# speedmeter.net
KiCad netlist of a schematic drawn in EAGLE
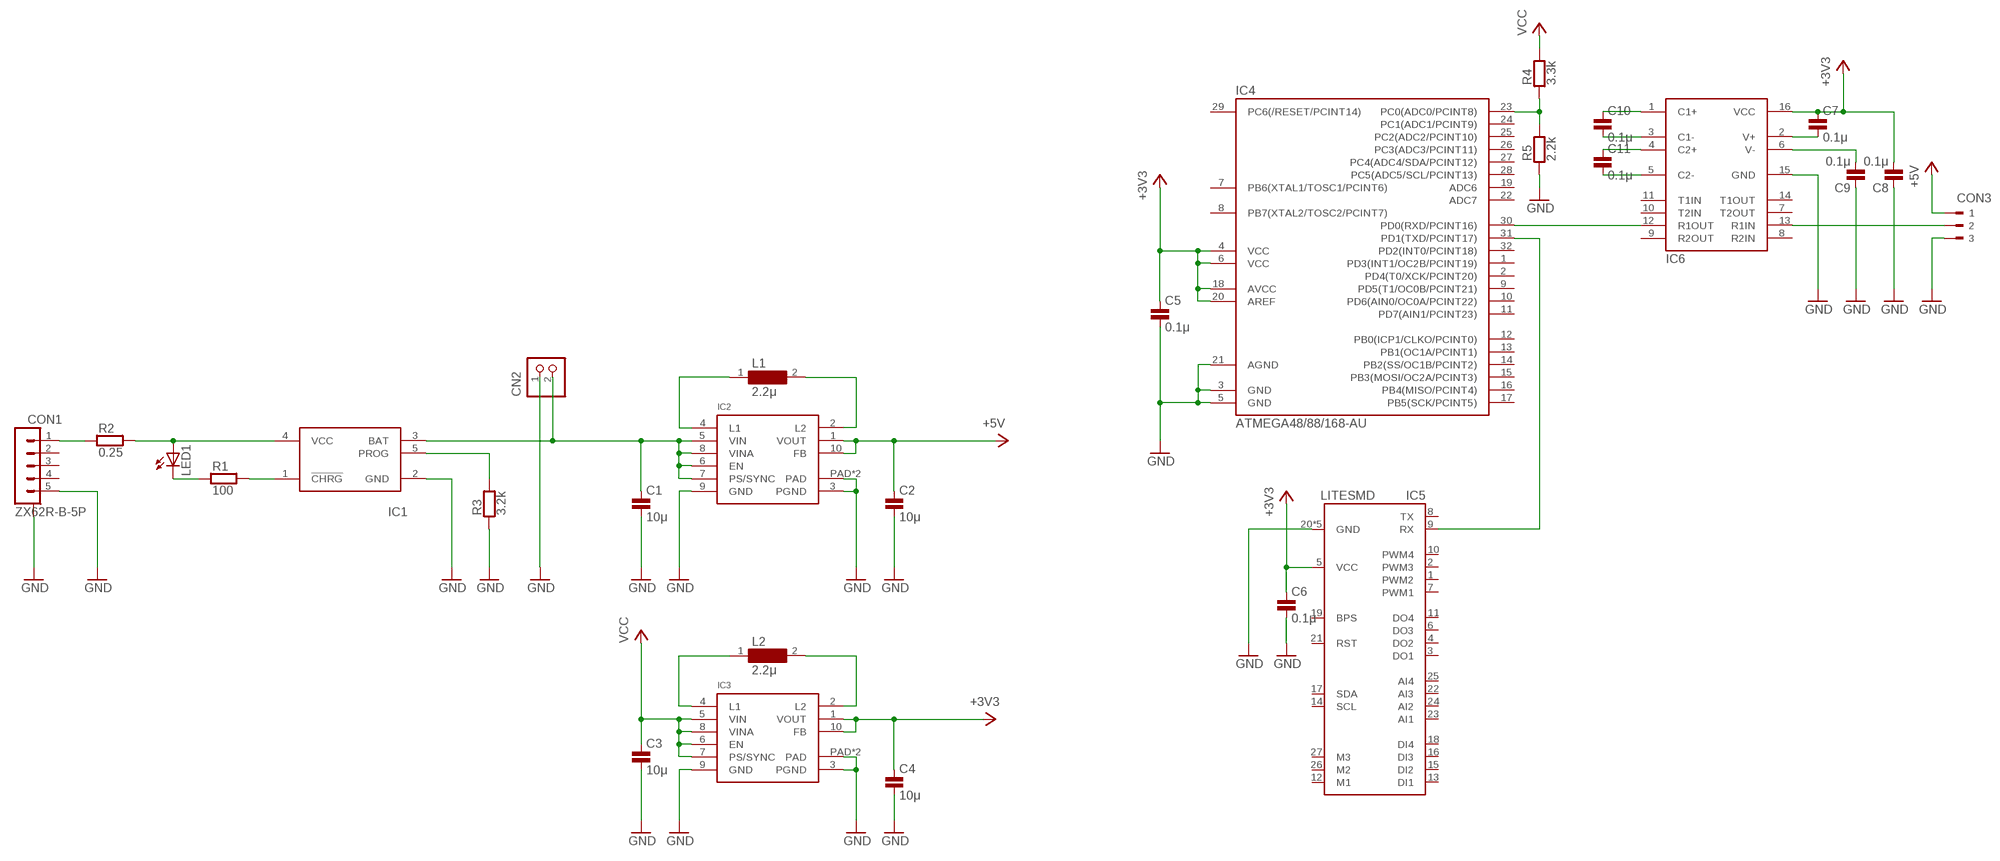
[diagram p0: schematic, sheet 1]

(export (version "E")
  (design (tool "Eeschema 10.0.6"))
  (components
    (comp (ref "C1")
      (value "10μ")
      (footprint "eagle-import:0603")
      (libsource (lib "eagle-import") (part "C0603"))
    )
    (comp (ref "C2")
      (value "10μ")
      (footprint "eagle-import:0603")
      (libsource (lib "eagle-import") (part "C0603"))
    )
    (comp (ref "C3")
      (value "10μ")
      (footprint "eagle-import:0603")
      (libsource (lib "eagle-import") (part "C0603"))
    )
    (comp (ref "C4")
      (value "10μ")
      (footprint "eagle-import:0603")
      (libsource (lib "eagle-import") (part "C0603"))
    )
    (comp (ref "C5")
      (value "0.1μ")
      (footprint "eagle-import:0603")
      (libsource (lib "eagle-import") (part "C0603"))
    )
    (comp (ref "C6")
      (value "0.1μ")
      (footprint "eagle-import:0603")
      (libsource (lib "eagle-import") (part "C0603"))
    )
    (comp (ref "C7")
      (value "0.1μ")
      (footprint "eagle-import:0603")
      (libsource (lib "eagle-import") (part "untitled-2_C0603"))
    )
    (comp (ref "C8")
      (value "0.1μ")
      (footprint "eagle-import:0603")
      (libsource (lib "eagle-import") (part "untitled-2_C0603"))
    )
    (comp (ref "C9")
      (value "0.1μ")
      (footprint "eagle-import:0603")
      (libsource (lib "eagle-import") (part "untitled-2_C0603"))
    )
    (comp (ref "C10")
      (value "0.1μ")
      (footprint "eagle-import:0603")
      (libsource (lib "eagle-import") (part "untitled-2_C0603"))
    )
    (comp (ref "C11")
      (value "0.1μ")
      (footprint "eagle-import:0603")
      (libsource (lib "eagle-import") (part "untitled-2_C0603"))
    )
    (comp (ref "CN2")
      (value "S2B-PH-K-S")
      (footprint "eagle-import:S2B-PH-K-S")
      (libsource (lib "eagle-import") (part "S2B-PH-K-S"))
    )
    (comp (ref "CON1")
      (value "ZX62R-B-5P")
      (footprint "eagle-import:MICRO-B")
      (libsource (lib "eagle-import") (part "ZX62R-B-5P"))
    )
    (comp (ref "CON3")
      (value "180-3")
      (footprint "eagle-import:180-3")
      (libsource (lib "eagle-import") (part "180-3"))
    )
    (comp (ref "IC1")
      (value "LTC4054")
      (footprint "eagle-import:TSOT23-5")
      (libsource (lib "eagle-import") (part "LTC4054"))
    )
    (comp (ref "IC2")
      (value "TPS6300XDRCT")
      (footprint "eagle-import:S-PVSON-N10")
      (libsource (lib "eagle-import") (part "TPS6300XDRCT"))
    )
    (comp (ref "IC3")
      (value "TPS6300XDRCT")
      (footprint "eagle-import:S-PVSON-N10")
      (libsource (lib "eagle-import") (part "TPS6300XDRCT"))
    )
    (comp (ref "IC4")
      (value "ATMEGA48/88/168-AU")
      (footprint "eagle-import:TQFP32-08")
      (libsource (lib "eagle-import") (part "ATMEGA48/88/168-AU"))
    )
    (comp (ref "IC5")
      (value "LITESMD")
      (footprint "eagle-import:LITE")
      (libsource (lib "eagle-import") (part "LITESMD"))
    )
    (comp (ref "IC6")
      (value "ADM3202ARN")
      (footprint "eagle-import:SOP16")
      (libsource (lib "eagle-import") (part "ADM3202ARN"))
    )
    (comp (ref "L1")
      (value "2.2μ")
      (footprint "eagle-import:VLF4012ST")
      (libsource (lib "eagle-import") (part "VLF4012ST"))
    )
    (comp (ref "L2")
      (value "2.2μ")
      (footprint "eagle-import:VLF4012ST")
      (libsource (lib "eagle-import") (part "VLF4012ST"))
    )
    (comp (ref "LED1")
      (value "LEDSML0603")
      (footprint "eagle-import:SML0603")
      (libsource (lib "eagle-import") (part "LEDSML0603"))
    )
    (comp (ref "R1")
      (value "100")
      (footprint "eagle-import:0603")
      (libsource (lib "eagle-import") (part "R0603"))
    )
    (comp (ref "R2")
      (value "0.25")
      (footprint "eagle-import:0603")
      (libsource (lib "eagle-import") (part "R0603"))
    )
    (comp (ref "R3")
      (value "3.2k")
      (footprint "eagle-import:0603")
      (libsource (lib "eagle-import") (part "R0603"))
    )
    (comp (ref "R4")
      (value "3.3k")
      (footprint "eagle-import:0603")
      (libsource (lib "eagle-import") (part "R0603"))
    )
    (comp (ref "R5")
      (value "2.2k")
      (footprint "eagle-import:0603")
      (libsource (lib "eagle-import") (part "R0603"))
    )
  )
  (nets
    (net (code "1") (name "+3V3") (class "Default")
      (node (ref "C4") (pin "1") (pinfunction "P$1_1") (pintype "passive"))
      (node (ref "C5") (pin "1") (pinfunction "P$1_1") (pintype "passive"))
      (node (ref "C6") (pin "1") (pinfunction "P$1_1") (pintype "passive"))
      (node (ref "C7") (pin "1") (pinfunction "P$1_1") (pintype "passive"))
      (node (ref "C8") (pin "2") (pinfunction "P$2_2") (pintype "passive"))
      (node (ref "IC3") (pin "1") (pinfunction "VOUT_1") (pintype "output"))
      (node (ref "IC3") (pin "10") (pinfunction "FB_10") (pintype "input"))
      (node (ref "IC4") (pin "18") (pinfunction "AVCC_18") (pintype "passive"))
      (node (ref "IC4") (pin "20") (pinfunction "AREF_20") (pintype "passive"))
      (node (ref "IC4") (pin "4") (pinfunction "VCC_4") (pintype "power_in"))
      (node (ref "IC4") (pin "6") (pinfunction "VCC_6") (pintype "power_in"))
      (node (ref "IC5") (pin "5") (pinfunction "VCC_5") (pintype "power_in"))
      (node (ref "IC6") (pin "16") (pinfunction "VCC_16") (pintype "bidirectional"))
    )
    (net (code "2") (name "+5V") (class "Default")
      (node (ref "C2") (pin "1") (pinfunction "P$1_1") (pintype "passive"))
      (node (ref "CON3") (pin "1") (pinfunction "1_1") (pintype "passive"))
      (node (ref "IC2") (pin "1") (pinfunction "VOUT_1") (pintype "output"))
      (node (ref "IC2") (pin "10") (pinfunction "FB_10") (pintype "input"))
    )
    (net (code "3") (name "GND") (class "Default")
      (node (ref "C1") (pin "2") (pinfunction "P$2_2") (pintype "passive"))
      (node (ref "C2") (pin "2") (pinfunction "P$2_2") (pintype "passive"))
      (node (ref "C3") (pin "2") (pinfunction "P$2_2") (pintype "passive"))
      (node (ref "C4") (pin "2") (pinfunction "P$2_2") (pintype "passive"))
      (node (ref "C5") (pin "2") (pinfunction "P$2_2") (pintype "passive"))
      (node (ref "C6") (pin "2") (pinfunction "P$2_2") (pintype "passive"))
      (node (ref "C8") (pin "1") (pinfunction "P$1_1") (pintype "passive"))
      (node (ref "C9") (pin "1") (pinfunction "P$1_1") (pintype "passive"))
      (node (ref "CN2") (pin "1") (pinfunction "1_1") (pintype "passive"))
      (node (ref "CON1") (pin "5") (pinfunction "1.VBUS_5") (pintype "passive"))
      (node (ref "CON1") (pin "CASE@1") (pinfunction "P$1_CASE@1") (pintype "bidirectional"))
      (node (ref "CON1") (pin "CASE@2") (pinfunction "P$1_CASE@2") (pintype "bidirectional"))
      (node (ref "CON1") (pin "CASE@3") (pinfunction "P$1_CASE@3") (pintype "bidirectional"))
      (node (ref "CON1") (pin "CASE@4") (pinfunction "P$1_CASE@4") (pintype "bidirectional"))
      (node (ref "CON3") (pin "3") (pinfunction "3_3") (pintype "passive"))
      (node (ref "IC1") (pin "2") (pinfunction "GND_2") (pintype "power_in"))
      (node (ref "IC2") (pin "3") (pinfunction "PGND_3") (pintype "power_in"))
      (node (ref "IC2") (pin "9") (pinfunction "GND_9") (pintype "power_in"))
      (node (ref "IC2") (pin "PAD") (pinfunction "PAD_PAD") (pintype "power_in"))
      (node (ref "IC2") (pin "PAD@1") (pinfunction "PAD_PAD@1") (pintype "power_in"))
      (node (ref "IC3") (pin "3") (pinfunction "PGND_3") (pintype "power_in"))
      (node (ref "IC3") (pin "9") (pinfunction "GND_9") (pintype "power_in"))
      (node (ref "IC3") (pin "PAD") (pinfunction "PAD_PAD") (pintype "power_in"))
      (node (ref "IC3") (pin "PAD@1") (pinfunction "PAD_PAD@1") (pintype "power_in"))
      (node (ref "IC4") (pin "21") (pinfunction "AGND_21") (pintype "power_in"))
      (node (ref "IC4") (pin "3") (pinfunction "GND_3") (pintype "power_in"))
      (node (ref "IC4") (pin "5") (pinfunction "GND_5") (pintype "power_in"))
      (node (ref "IC5") (pin "20") (pinfunction "GND_20") (pintype "power_in"))
      (node (ref "IC5") (pin "28") (pinfunction "GND_28") (pintype "power_in"))
      (node (ref "IC5") (pin "30") (pinfunction "GND_30") (pintype "power_in"))
      (node (ref "IC5") (pin "31") (pinfunction "GND_31") (pintype "power_in"))
      (node (ref "IC5") (pin "32") (pinfunction "GND_32") (pintype "power_in"))
      (node (ref "IC6") (pin "15") (pinfunction "GND_15") (pintype "bidirectional"))
      (node (ref "R3") (pin "1") (pinfunction "P$1_1") (pintype "passive"))
      (node (ref "R5") (pin "1") (pinfunction "P$1_1") (pintype "passive"))
    )
    (net (code "4") (name "Net-(C7-P$2)") (class "Default")
      (node (ref "C7") (pin "2") (pinfunction "P$2_2") (pintype "passive"))
      (node (ref "IC6") (pin "2") (pinfunction "V+_2") (pintype "bidirectional"))
    )
    (net (code "5") (name "Net-(C9-P$2)") (class "Default")
      (node (ref "C9") (pin "2") (pinfunction "P$2_2") (pintype "passive"))
      (node (ref "IC6") (pin "6") (pinfunction "V-_6") (pintype "bidirectional"))
    )
    (net (code "6") (name "Net-(C10-P$1)") (class "Default")
      (node (ref "C10") (pin "1") (pinfunction "P$1_1") (pintype "passive"))
      (node (ref "IC6") (pin "1") (pinfunction "C1+_1") (pintype "bidirectional"))
    )
    (net (code "7") (name "Net-(C10-P$2)") (class "Default")
      (node (ref "C10") (pin "2") (pinfunction "P$2_2") (pintype "passive"))
      (node (ref "IC6") (pin "3") (pinfunction "C1-_3") (pintype "bidirectional"))
    )
    (net (code "8") (name "Net-(C11-P$1)") (class "Default")
      (node (ref "C11") (pin "1") (pinfunction "P$1_1") (pintype "passive"))
      (node (ref "IC6") (pin "4") (pinfunction "C2+_4") (pintype "bidirectional"))
    )
    (net (code "9") (name "Net-(C11-P$2)") (class "Default")
      (node (ref "C11") (pin "2") (pinfunction "P$2_2") (pintype "passive"))
      (node (ref "IC6") (pin "5") (pinfunction "C2-_5") (pintype "bidirectional"))
    )
    (net (code "10") (name "Net-(CON1-5.GND)") (class "Default")
      (node (ref "CON1") (pin "1") (pinfunction "5.GND_1") (pintype "passive"))
      (node (ref "R2") (pin "1") (pinfunction "P$1_1") (pintype "passive"))
    )
    (net (code "11") (name "Net-(IC1-PROG)") (class "Default")
      (node (ref "IC1") (pin "5") (pinfunction "PROG_5") (pintype "passive"))
      (node (ref "R3") (pin "2") (pinfunction "P$2_2") (pintype "passive"))
    )
    (net (code "12") (name "Net-(IC1-VCC)") (class "Default")
      (node (ref "IC1") (pin "4") (pinfunction "VCC_4") (pintype "power_in"))
      (node (ref "LED1") (pin "A") (pinfunction "A_A") (pintype "passive"))
      (node (ref "R2") (pin "2") (pinfunction "P$2_2") (pintype "passive"))
    )
    (net (code "13") (name "Net-(IC1-~{CHRG})") (class "Default")
      (node (ref "IC1") (pin "1") (pinfunction "~{CHRG}_1") (pintype "output"))
      (node (ref "R1") (pin "2") (pinfunction "P$2_2") (pintype "passive"))
    )
    (net (code "14") (name "Net-(IC2-L1)") (class "Default")
      (node (ref "IC2") (pin "4") (pinfunction "L1_4") (pintype "bidirectional"))
      (node (ref "L1") (pin "1") (pinfunction "1_1") (pintype "passive"))
    )
    (net (code "15") (name "Net-(IC2-L2)") (class "Default")
      (node (ref "IC2") (pin "2") (pinfunction "L2_2") (pintype "bidirectional"))
      (node (ref "L1") (pin "2") (pinfunction "2_2") (pintype "passive"))
    )
    (net (code "16") (name "Net-(IC3-L1)") (class "Default")
      (node (ref "IC3") (pin "4") (pinfunction "L1_4") (pintype "bidirectional"))
      (node (ref "L2") (pin "1") (pinfunction "1_1") (pintype "passive"))
    )
    (net (code "17") (name "Net-(IC3-L2)") (class "Default")
      (node (ref "IC3") (pin "2") (pinfunction "L2_2") (pintype "bidirectional"))
      (node (ref "L2") (pin "2") (pinfunction "2_2") (pintype "passive"))
    )
    (net (code "18") (name "Net-(IC4-PC0(ADC0{slash}PCINT8))") (class "Default")
      (node (ref "IC4") (pin "23") (pinfunction "PC0(ADC0/PCINT8)_23") (pintype "bidirectional"))
      (node (ref "R4") (pin "1") (pinfunction "P$1_1") (pintype "passive"))
      (node (ref "R5") (pin "2") (pinfunction "P$2_2") (pintype "passive"))
    )
    (net (code "19") (name "Net-(IC4-PD0(RXD{slash}PCINT16))") (class "Default")
      (node (ref "IC4") (pin "30") (pinfunction "PD0(RXD/PCINT16)_30") (pintype "bidirectional"))
      (node (ref "IC6") (pin "12") (pinfunction "R1OUT_12") (pintype "bidirectional"))
    )
    (net (code "20") (name "Net-(IC4-PD1(TXD{slash}PCINT17))") (class "Default")
      (node (ref "IC4") (pin "31") (pinfunction "PD1(TXD/PCINT17)_31") (pintype "bidirectional"))
      (node (ref "IC5") (pin "9") (pinfunction "RX_9") (pintype "input"))
    )
    (net (code "21") (name "Net-(IC6-R1IN)") (class "Default")
      (node (ref "CON3") (pin "2") (pinfunction "2_2") (pintype "passive"))
      (node (ref "IC6") (pin "13") (pinfunction "R1IN_13") (pintype "bidirectional"))
    )
    (net (code "22") (name "Net-(R1-P$1)") (class "Default")
      (node (ref "LED1") (pin "C") (pinfunction "C_C") (pintype "passive"))
      (node (ref "R1") (pin "1") (pinfunction "P$1_1") (pintype "passive"))
    )
    (net (code "23") (name "VCC") (class "Default")
      (node (ref "C1") (pin "1") (pinfunction "P$1_1") (pintype "passive"))
      (node (ref "C3") (pin "1") (pinfunction "P$1_1") (pintype "passive"))
      (node (ref "CN2") (pin "2") (pinfunction "2_2") (pintype "passive"))
      (node (ref "IC1") (pin "3") (pinfunction "BAT_3") (pintype "power_in"))
      (node (ref "IC2") (pin "5") (pinfunction "VIN_5") (pintype "power_in"))
      (node (ref "IC2") (pin "6") (pinfunction "EN_6") (pintype "input"))
      (node (ref "IC2") (pin "7") (pinfunction "PS/SYNC_7") (pintype "input"))
      (node (ref "IC2") (pin "8") (pinfunction "VINA_8") (pintype "power_in"))
      (node (ref "IC3") (pin "5") (pinfunction "VIN_5") (pintype "power_in"))
      (node (ref "IC3") (pin "6") (pinfunction "EN_6") (pintype "input"))
      (node (ref "IC3") (pin "7") (pinfunction "PS/SYNC_7") (pintype "input"))
      (node (ref "IC3") (pin "8") (pinfunction "VINA_8") (pintype "power_in"))
      (node (ref "R4") (pin "2") (pinfunction "P$2_2") (pintype "passive"))
    )
    (net (code "24") (name "unconnected-(CON1-2.D--Pad4)") (class "Default")
      (node (ref "CON1") (pin "4") (pinfunction "2.D-_4") (pintype "passive"))
    )
    (net (code "25") (name "unconnected-(CON1-3.D+-Pad3)") (class "Default")
      (node (ref "CON1") (pin "3") (pinfunction "3.D+_3") (pintype "passive"))
    )
    (net (code "26") (name "unconnected-(CON1-4.ID-Pad2)") (class "Default")
      (node (ref "CON1") (pin "2") (pinfunction "4.ID_2") (pintype "passive"))
    )
    (net (code "27") (name "unconnected-(IC4-ADC6-Pad19)") (class "Default")
      (node (ref "IC4") (pin "19") (pinfunction "ADC6_19") (pintype "passive"))
    )
    (net (code "28") (name "unconnected-(IC4-ADC7-Pad22)") (class "Default")
      (node (ref "IC4") (pin "22") (pinfunction "ADC7_22") (pintype "passive"))
    )
    (net (code "29") (name "unconnected-(IC4-PB0(ICP1{slash}CLKO{slash}PCINT0)-Pad12)") (class "Default")
      (node (ref "IC4") (pin "12") (pinfunction "PB0(ICP1/CLKO/PCINT0)_12") (pintype "bidirectional"))
    )
    (net (code "30") (name "unconnected-(IC4-PB1(OC1A{slash}PCINT1)-Pad13)") (class "Default")
      (node (ref "IC4") (pin "13") (pinfunction "PB1(OC1A/PCINT1)_13") (pintype "bidirectional"))
    )
    (net (code "31") (name "unconnected-(IC4-PB2(SS{slash}OC1B{slash}PCINT2)-Pad14)") (class "Default")
      (node (ref "IC4") (pin "14") (pinfunction "PB2(SS/OC1B/PCINT2)_14") (pintype "bidirectional"))
    )
    (net (code "32") (name "unconnected-(IC4-PB3(MOSI{slash}OC2A{slash}PCINT3)-Pad15)") (class "Default")
      (node (ref "IC4") (pin "15") (pinfunction "PB3(MOSI/OC2A/PCINT3)_15") (pintype "bidirectional"))
    )
    (net (code "33") (name "unconnected-(IC4-PB4(MISO{slash}PCINT4)-Pad16)") (class "Default")
      (node (ref "IC4") (pin "16") (pinfunction "PB4(MISO/PCINT4)_16") (pintype "bidirectional"))
    )
    (net (code "34") (name "unconnected-(IC4-PB5(SCK{slash}PCINT5)-Pad17)") (class "Default")
      (node (ref "IC4") (pin "17") (pinfunction "PB5(SCK/PCINT5)_17") (pintype "bidirectional"))
    )
    (net (code "35") (name "unconnected-(IC4-PB6(XTAL1{slash}TOSC1{slash}PCINT6)-Pad7)") (class "Default")
      (node (ref "IC4") (pin "7") (pinfunction "PB6(XTAL1/TOSC1/PCINT6)_7") (pintype "bidirectional"))
    )
    (net (code "36") (name "unconnected-(IC4-PB7(XTAL2{slash}TOSC2{slash}PCINT7)-Pad8)") (class "Default")
      (node (ref "IC4") (pin "8") (pinfunction "PB7(XTAL2/TOSC2/PCINT7)_8") (pintype "bidirectional"))
    )
    (net (code "37") (name "unconnected-(IC4-PC1(ADC1{slash}PCINT9)-Pad24)") (class "Default")
      (node (ref "IC4") (pin "24") (pinfunction "PC1(ADC1/PCINT9)_24") (pintype "bidirectional"))
    )
    (net (code "38") (name "unconnected-(IC4-PC2(ADC2{slash}PCINT10)-Pad25)") (class "Default")
      (node (ref "IC4") (pin "25") (pinfunction "PC2(ADC2/PCINT10)_25") (pintype "bidirectional"))
    )
    (net (code "39") (name "unconnected-(IC4-PC3(ADC3{slash}PCINT11)-Pad26)") (class "Default")
      (node (ref "IC4") (pin "26") (pinfunction "PC3(ADC3/PCINT11)_26") (pintype "bidirectional"))
    )
    (net (code "40") (name "unconnected-(IC4-PC4(ADC4{slash}SDA{slash}PCINT12)-Pad27)") (class "Default")
      (node (ref "IC4") (pin "27") (pinfunction "PC4(ADC4/SDA/PCINT12)_27") (pintype "bidirectional"))
    )
    (net (code "41") (name "unconnected-(IC4-PC5(ADC5{slash}SCL{slash}PCINT13)-Pad28)") (class "Default")
      (node (ref "IC4") (pin "28") (pinfunction "PC5(ADC5/SCL/PCINT13)_28") (pintype "bidirectional"))
    )
    (net (code "42") (name "unconnected-(IC4-PC6({slash}RESET{slash}PCINT14)-Pad29)") (class "Default")
      (node (ref "IC4") (pin "29") (pinfunction "PC6(/RESET/PCINT14)_29") (pintype "bidirectional"))
    )
    (net (code "43") (name "unconnected-(IC4-PD2(INT0{slash}PCINT18)-Pad32)") (class "Default")
      (node (ref "IC4") (pin "32") (pinfunction "PD2(INT0/PCINT18)_32") (pintype "bidirectional"))
    )
    (net (code "44") (name "unconnected-(IC4-PD3(INT1{slash}OC2B{slash}PCINT19)-Pad1)") (class "Default")
      (node (ref "IC4") (pin "1") (pinfunction "PD3(INT1/OC2B/PCINT19)_1") (pintype "bidirectional"))
    )
    (net (code "45") (name "unconnected-(IC4-PD4(T0{slash}XCK{slash}PCINT20)-Pad2)") (class "Default")
      (node (ref "IC4") (pin "2") (pinfunction "PD4(T0/XCK/PCINT20)_2") (pintype "bidirectional"))
    )
    (net (code "46") (name "unconnected-(IC4-PD5(T1{slash}OC0B{slash}PCINT21)-Pad9)") (class "Default")
      (node (ref "IC4") (pin "9") (pinfunction "PD5(T1/OC0B/PCINT21)_9") (pintype "bidirectional"))
    )
    (net (code "47") (name "unconnected-(IC4-PD6(AIN0{slash}OC0A{slash}PCINT22)-Pad10)") (class "Default")
      (node (ref "IC4") (pin "10") (pinfunction "PD6(AIN0/OC0A/PCINT22)_10") (pintype "bidirectional"))
    )
    (net (code "48") (name "unconnected-(IC4-PD7(AIN1{slash}PCINT23)-Pad11)") (class "Default")
      (node (ref "IC4") (pin "11") (pinfunction "PD7(AIN1/PCINT23)_11") (pintype "bidirectional"))
    )
    (net (code "49") (name "unconnected-(IC5-AI1-Pad23)") (class "Default")
      (node (ref "IC5") (pin "23") (pinfunction "AI1_23") (pintype "input"))
    )
    (net (code "50") (name "unconnected-(IC5-AI2-Pad24)") (class "Default")
      (node (ref "IC5") (pin "24") (pinfunction "AI2_24") (pintype "input"))
    )
    (net (code "51") (name "unconnected-(IC5-AI3-Pad22)") (class "Default")
      (node (ref "IC5") (pin "22") (pinfunction "AI3_22") (pintype "input"))
    )
    (net (code "52") (name "unconnected-(IC5-AI4-Pad25)") (class "Default")
      (node (ref "IC5") (pin "25") (pinfunction "AI4_25") (pintype "input"))
    )
    (net (code "53") (name "unconnected-(IC5-BPS-Pad19)") (class "Default")
      (node (ref "IC5") (pin "19") (pinfunction "BPS_19") (pintype "input"))
    )
    (net (code "54") (name "unconnected-(IC5-DI1-Pad13)") (class "Default")
      (node (ref "IC5") (pin "13") (pinfunction "DI1_13") (pintype "input"))
    )
    (net (code "55") (name "unconnected-(IC5-DI2-Pad15)") (class "Default")
      (node (ref "IC5") (pin "15") (pinfunction "DI2_15") (pintype "input"))
    )
    (net (code "56") (name "unconnected-(IC5-DI3-Pad16)") (class "Default")
      (node (ref "IC5") (pin "16") (pinfunction "DI3_16") (pintype "input"))
    )
    (net (code "57") (name "unconnected-(IC5-DI4-Pad18)") (class "Default")
      (node (ref "IC5") (pin "18") (pinfunction "DI4_18") (pintype "input"))
    )
    (net (code "58") (name "unconnected-(IC5-DO1-Pad3)") (class "Default")
      (node (ref "IC5") (pin "3") (pinfunction "DO1_3") (pintype "output"))
    )
    (net (code "59") (name "unconnected-(IC5-DO2-Pad4)") (class "Default")
      (node (ref "IC5") (pin "4") (pinfunction "DO2_4") (pintype "output"))
    )
    (net (code "60") (name "unconnected-(IC5-DO3-Pad6)") (class "Default")
      (node (ref "IC5") (pin "6") (pinfunction "DO3_6") (pintype "output"))
    )
    (net (code "61") (name "unconnected-(IC5-DO4-Pad11)") (class "Default")
      (node (ref "IC5") (pin "11") (pinfunction "DO4_11") (pintype "output"))
    )
    (net (code "62") (name "unconnected-(IC5-M1-Pad12)") (class "Default")
      (node (ref "IC5") (pin "12") (pinfunction "M1_12") (pintype "input"))
    )
    (net (code "63") (name "unconnected-(IC5-M2-Pad26)") (class "Default")
      (node (ref "IC5") (pin "26") (pinfunction "M2_26") (pintype "input"))
    )
    (net (code "64") (name "unconnected-(IC5-M3-Pad27)") (class "Default")
      (node (ref "IC5") (pin "27") (pinfunction "M3_27") (pintype "input"))
    )
    (net (code "65") (name "unconnected-(IC5-PWM1-Pad7)") (class "Default")
      (node (ref "IC5") (pin "7") (pinfunction "PWM1_7") (pintype "output"))
    )
    (net (code "66") (name "unconnected-(IC5-PWM2-Pad1)") (class "Default")
      (node (ref "IC5") (pin "1") (pinfunction "PWM2_1") (pintype "output"))
    )
    (net (code "67") (name "unconnected-(IC5-PWM3-Pad2)") (class "Default")
      (node (ref "IC5") (pin "2") (pinfunction "PWM3_2") (pintype "output"))
    )
    (net (code "68") (name "unconnected-(IC5-PWM4-Pad10)") (class "Default")
      (node (ref "IC5") (pin "10") (pinfunction "PWM4_10") (pintype "output"))
    )
    (net (code "69") (name "unconnected-(IC5-RST-Pad21)") (class "Default")
      (node (ref "IC5") (pin "21") (pinfunction "RST_21") (pintype "input"))
    )
    (net (code "70") (name "unconnected-(IC5-SCL-Pad14)") (class "Default")
      (node (ref "IC5") (pin "14") (pinfunction "SCL_14") (pintype "bidirectional"))
    )
    (net (code "71") (name "unconnected-(IC5-SDA-Pad17)") (class "Default")
      (node (ref "IC5") (pin "17") (pinfunction "SDA_17") (pintype "bidirectional"))
    )
    (net (code "72") (name "unconnected-(IC5-TX-Pad8)") (class "Default")
      (node (ref "IC5") (pin "8") (pinfunction "TX_8") (pintype "output"))
    )
    (net (code "73") (name "unconnected-(IC6-R2IN-Pad8)") (class "Default")
      (node (ref "IC6") (pin "8") (pinfunction "R2IN_8") (pintype "bidirectional"))
    )
    (net (code "74") (name "unconnected-(IC6-R2OUT-Pad9)") (class "Default")
      (node (ref "IC6") (pin "9") (pinfunction "R2OUT_9") (pintype "bidirectional"))
    )
    (net (code "75") (name "unconnected-(IC6-T1IN-Pad11)") (class "Default")
      (node (ref "IC6") (pin "11") (pinfunction "T1IN_11") (pintype "bidirectional"))
    )
    (net (code "76") (name "unconnected-(IC6-T1OUT-Pad14)") (class "Default")
      (node (ref "IC6") (pin "14") (pinfunction "T1OUT_14") (pintype "bidirectional"))
    )
    (net (code "77") (name "unconnected-(IC6-T2IN-Pad10)") (class "Default")
      (node (ref "IC6") (pin "10") (pinfunction "T2IN_10") (pintype "bidirectional"))
    )
    (net (code "78") (name "unconnected-(IC6-T2OUT-Pad7)") (class "Default")
      (node (ref "IC6") (pin "7") (pinfunction "T2OUT_7") (pintype "bidirectional"))
    )
  )
)
